# sch_LIMA_Driver.net
KiCad netlist of a schematic drawn in Altium Designer
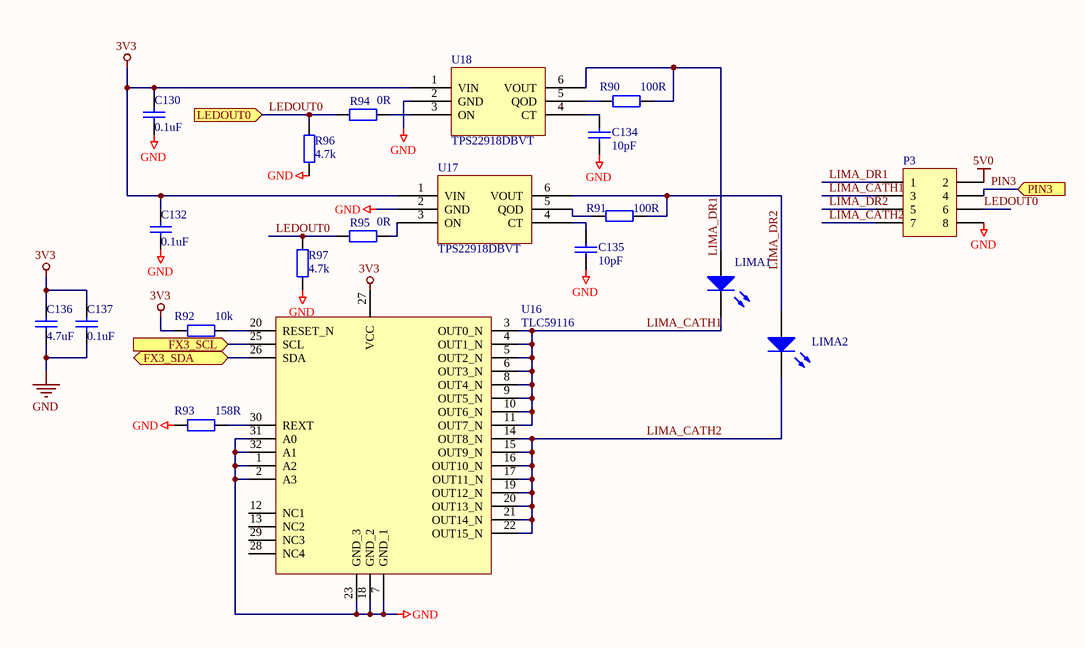
[diagram p0: sch_LIMA_Driver.SchDoc]

(export (version "E")
  (design (tool "Eeschema 10.0.6"))
  (components
    (comp (ref "C130")
      (value "0.1uF")
      (footprint "0402C_L")
      (description "Capacitor")
      (fields (field (name "Comment") "1uF") (field (name "PUBLISHER") "Altium Limited"))
      (libsource (lib "Miscellaneous Devices") (part "Cap"))
    )
    (comp (ref "C132")
      (value "0.1uF")
      (footprint "0402C_L")
      (description "Capacitor")
      (fields (field (name "Comment") "1uF") (field (name "PUBLISHER") "Altium Limited"))
      (libsource (lib "Miscellaneous Devices") (part "Cap"))
    )
    (comp (ref "C134")
      (value "10pF")
      (footprint "0402C_L")
      (description "Capacitor")
      (fields (field (name "PUBLISHER") "Altium Limited"))
      (libsource (lib "Miscellaneous Devices") (part "Cap"))
    )
    (comp (ref "C135")
      (value "10pF")
      (footprint "0402C_L")
      (description "Capacitor")
      (fields (field (name "PUBLISHER") "Altium Limited"))
      (libsource (lib "Miscellaneous Devices") (part "Cap"))
    )
    (comp (ref "C136")
      (value "4.7uF")
      (description "Capacitor")
      (fields (field (name "PUBLISHER") "Altium Limited"))
      (libsource (lib "Miscellaneous Devices") (part "Cap"))
    )
    (comp (ref "C137")
      (value "0.1uF")
      (footprint "0402C")
      (description "Capacitor")
      (fields (field (name "PUBLISHER") "Altium Limited"))
      (libsource (lib "Miscellaneous Devices") (part "Cap"))
    )
    (comp (ref "LIMA1") (value "LIMA") (description "发光二级管") (libsource (lib "TXW") (part "LED")))
    (comp (ref "LIMA2") (value "LIMA") (description "发光二级管") (libsource (lib "TXW") (part "LED")))
    (comp (ref "P3")
      (value "Header 4X2")
      (footprint "HDR2X4")
      (description "Header, 4-Pin, Dual row")
      (fields (field (name "PUBLISHER") "Altium Limited"))
      (libsource (lib "SZG") (part "Header 4X2"))
    )
    (comp (ref "R90")
      (value "100R")
      (footprint "0402R")
      (description "Resistor")
      (fields (field (name "PUBLISHER") "Altium Limited"))
      (libsource (lib "") (part "Resistor_1"))
    )
    (comp (ref "R91")
      (value "100R")
      (footprint "0402R")
      (description "Resistor")
      (fields (field (name "PUBLISHER") "Altium Limited"))
      (libsource (lib "") (part "Resistor_1"))
    )
    (comp (ref "R92")
      (value "10k")
      (footprint "0402R")
      (description "Resistor")
      (fields (field (name "PUBLISHER") "Altium Limited"))
      (libsource (lib "") (part "Resistor_1"))
    )
    (comp (ref "R93")
      (value "158R")
      (footprint "0402R")
      (description "Resistor")
      (fields (field (name "PUBLISHER") "Altium Limited"))
      (libsource (lib "") (part "Resistor_1"))
    )
    (comp (ref "R94")
      (value "0R")
      (footprint "0402R")
      (description "Resistor")
      (fields (field (name "PUBLISHER") "Altium Limited"))
      (libsource (lib "") (part "Resistor_1"))
    )
    (comp (ref "R95")
      (value "0R")
      (footprint "0402R")
      (description "Resistor")
      (fields (field (name "PUBLISHER") "Altium Limited"))
      (libsource (lib "") (part "Resistor_1"))
    )
    (comp (ref "R96")
      (value "4.7k")
      (footprint "0402R")
      (description "Resistor")
      (fields (field (name "PUBLISHER") "Altium Limited"))
      (libsource (lib "SZG") (part "Resistor"))
    )
    (comp (ref "R97")
      (value "4.7k")
      (footprint "0402R")
      (description "Resistor")
      (fields (field (name "PUBLISHER") "Altium Limited"))
      (libsource (lib "SZG") (part "Resistor"))
    )
    (comp (ref "U16") (value "TLC59116") (libsource (lib "SZG") (part "TLC59116")))
    (comp (ref "U17") (value "TPS22918DBVT") (libsource (lib "SZG") (part "TPS22918DBVT")))
    (comp (ref "U18") (value "TPS22918DBVT") (libsource (lib "SZG") (part "TPS22918DBVT")))
  )
  (nets
    (net (code "1") (name "/FX3_SCL") (class "Default")
      (node (ref "U16") (pin "25") (pinfunction "SCL_25") (pintype "passive"))
    )
    (net (code "2") (name "/FX3_SDA") (class "Default")
      (node (ref "U16") (pin "26") (pinfunction "SDA_26") (pintype "passive"))
    )
    (net (code "3") (name "/LEDOUT0") (class "Default")
      (node (ref "P3") (pin "6") (pinfunction "6_6") (pintype "passive"))
      (node (ref "R94") (pin "2") (pinfunction "2_2") (pintype "passive"))
      (node (ref "R95") (pin "2") (pinfunction "2_2") (pintype "passive"))
      (node (ref "R96") (pin "2") (pinfunction "2_2") (pintype "passive"))
      (node (ref "R97") (pin "2") (pinfunction "2_2") (pintype "passive"))
    )
    (net (code "4") (name "/LIMA_CATH1") (class "Default")
      (node (ref "LIMA1") (pin "2") (pinfunction "K_2") (pintype "passive"))
      (node (ref "P3") (pin "3") (pinfunction "3_3") (pintype "passive"))
      (node (ref "U16") (pin "10") (pinfunction "OUT6_N_10") (pintype "passive"))
      (node (ref "U16") (pin "11") (pinfunction "OUT7_N_11") (pintype "passive"))
      (node (ref "U16") (pin "3") (pinfunction "OUT0_N_3") (pintype "passive"))
      (node (ref "U16") (pin "4") (pinfunction "OUT1_N_4") (pintype "passive"))
      (node (ref "U16") (pin "5") (pinfunction "OUT2_N_5") (pintype "passive"))
      (node (ref "U16") (pin "6") (pinfunction "OUT3_N_6") (pintype "passive"))
      (node (ref "U16") (pin "8") (pinfunction "OUT4_N_8") (pintype "passive"))
      (node (ref "U16") (pin "9") (pinfunction "OUT5_N_9") (pintype "passive"))
    )
    (net (code "5") (name "/LIMA_CATH2") (class "Default")
      (node (ref "LIMA2") (pin "2") (pinfunction "K_2") (pintype "passive"))
      (node (ref "P3") (pin "7") (pinfunction "7_7") (pintype "passive"))
      (node (ref "U16") (pin "14") (pinfunction "OUT8_N_14") (pintype "passive"))
      (node (ref "U16") (pin "15") (pinfunction "OUT9_N_15") (pintype "passive"))
      (node (ref "U16") (pin "16") (pinfunction "OUT10_N_16") (pintype "passive"))
      (node (ref "U16") (pin "17") (pinfunction "OUT11_N_17") (pintype "passive"))
      (node (ref "U16") (pin "19") (pinfunction "OUT12_N_19") (pintype "passive"))
      (node (ref "U16") (pin "20") (pinfunction "OUT13_N_20") (pintype "passive"))
      (node (ref "U16") (pin "21") (pinfunction "OUT14_N_21") (pintype "passive"))
      (node (ref "U16") (pin "22") (pinfunction "OUT15_N_22") (pintype "passive"))
    )
    (net (code "6") (name "/LIMA_DR1") (class "Default")
      (node (ref "P3") (pin "1") (pinfunction "1_1") (pintype "passive"))
    )
    (net (code "7") (name "/LIMA_DR2") (class "Default")
      (node (ref "LIMA2") (pin "1") (pinfunction "A_1") (pintype "passive"))
      (node (ref "P3") (pin "5") (pinfunction "5_5") (pintype "passive"))
      (node (ref "R91") (pin "1") (pinfunction "1_1") (pintype "passive"))
      (node (ref "U17") (pin "6") (pinfunction "VOUT_6") (pintype "passive"))
    )
    (net (code "8") (name "/PIN3") (class "Default")
      (node (ref "P3") (pin "4") (pinfunction "4_4") (pintype "passive"))
    )
    (net (code "9") (name "3V3") (class "Default")
      (node (ref "C130") (pin "2") (pinfunction "2_2") (pintype "passive"))
      (node (ref "C132") (pin "2") (pinfunction "2_2") (pintype "passive"))
      (node (ref "C136") (pin "2") (pinfunction "2_2") (pintype "passive"))
      (node (ref "C137") (pin "2") (pinfunction "2_2") (pintype "passive"))
      (node (ref "R92") (pin "2") (pinfunction "2_2") (pintype "passive"))
      (node (ref "U16") (pin "27") (pinfunction "VCC_27") (pintype "passive"))
      (node (ref "U17") (pin "1") (pinfunction "VIN_1") (pintype "passive"))
      (node (ref "U18") (pin "1") (pinfunction "VIN_1") (pintype "passive"))
    )
    (net (code "10") (name "5V0") (class "Default")
      (node (ref "P3") (pin "2") (pinfunction "2_2") (pintype "passive"))
    )
    (net (code "11") (name "GND") (class "Default")
      (node (ref "C130") (pin "1") (pinfunction "1_1") (pintype "passive"))
      (node (ref "C132") (pin "1") (pinfunction "1_1") (pintype "passive"))
      (node (ref "C134") (pin "1") (pinfunction "1_1") (pintype "passive"))
      (node (ref "C135") (pin "1") (pinfunction "1_1") (pintype "passive"))
      (node (ref "C136") (pin "1") (pinfunction "1_1") (pintype "passive"))
      (node (ref "C137") (pin "1") (pinfunction "1_1") (pintype "passive"))
      (node (ref "P3") (pin "8") (pinfunction "8_8") (pintype "passive"))
      (node (ref "R93") (pin "2") (pinfunction "2_2") (pintype "passive"))
      (node (ref "R96") (pin "1") (pinfunction "1_1") (pintype "passive"))
      (node (ref "R97") (pin "1") (pinfunction "1_1") (pintype "passive"))
      (node (ref "U16") (pin "1") (pinfunction "A2_1") (pintype "passive"))
      (node (ref "U16") (pin "18") (pinfunction "GND_2_18") (pintype "passive"))
      (node (ref "U16") (pin "2") (pinfunction "A3_2") (pintype "passive"))
      (node (ref "U16") (pin "23") (pinfunction "GND_3_23") (pintype "passive"))
      (node (ref "U16") (pin "31") (pinfunction "A0_31") (pintype "passive"))
      (node (ref "U16") (pin "32") (pinfunction "A1_32") (pintype "passive"))
      (node (ref "U16") (pin "7") (pinfunction "GND_1_7") (pintype "passive"))
      (node (ref "U17") (pin "2") (pinfunction "GND_2") (pintype "passive"))
      (node (ref "U18") (pin "2") (pinfunction "GND_2") (pintype "passive"))
    )
    (net (code "12") (name "Net-(LIMA1-A)") (class "Default")
      (node (ref "LIMA1") (pin "1") (pinfunction "A_1") (pintype "passive"))
      (node (ref "R90") (pin "1") (pinfunction "1_1") (pintype "passive"))
      (node (ref "U18") (pin "6") (pinfunction "VOUT_6") (pintype "passive"))
    )
    (net (code "13") (name "Net-(U16-RESET_N)") (class "Default")
      (node (ref "R92") (pin "1") (pinfunction "1_1") (pintype "passive"))
      (node (ref "U16") (pin "20") (pinfunction "RESET_N_20") (pintype "passive"))
    )
    (net (code "14") (name "Net-(U16-REXT)") (class "Default")
      (node (ref "R93") (pin "1") (pinfunction "1_1") (pintype "passive"))
      (node (ref "U16") (pin "30") (pinfunction "REXT_30") (pintype "passive"))
    )
    (net (code "15") (name "Net-(U17-CT)") (class "Default")
      (node (ref "C135") (pin "2") (pinfunction "2_2") (pintype "passive"))
      (node (ref "U17") (pin "4") (pinfunction "CT_4") (pintype "passive"))
    )
    (net (code "16") (name "Net-(U17-ON)") (class "Default")
      (node (ref "R95") (pin "1") (pinfunction "1_1") (pintype "passive"))
      (node (ref "U17") (pin "3") (pinfunction "ON_3") (pintype "passive"))
    )
    (net (code "17") (name "Net-(U17-QOD)") (class "Default")
      (node (ref "R91") (pin "2") (pinfunction "2_2") (pintype "passive"))
      (node (ref "U17") (pin "5") (pinfunction "QOD_5") (pintype "passive"))
    )
    (net (code "18") (name "Net-(U18-CT)") (class "Default")
      (node (ref "C134") (pin "2") (pinfunction "2_2") (pintype "passive"))
      (node (ref "U18") (pin "4") (pinfunction "CT_4") (pintype "passive"))
    )
    (net (code "19") (name "Net-(U18-ON)") (class "Default")
      (node (ref "R94") (pin "1") (pinfunction "1_1") (pintype "passive"))
      (node (ref "U18") (pin "3") (pinfunction "ON_3") (pintype "passive"))
    )
    (net (code "20") (name "Net-(U18-QOD)") (class "Default")
      (node (ref "R90") (pin "2") (pinfunction "2_2") (pintype "passive"))
      (node (ref "U18") (pin "5") (pinfunction "QOD_5") (pintype "passive"))
    )
    (net (code "21") (name "unconnected-(U16-NC1-Pad12)") (class "Default")
      (node (ref "U16") (pin "12") (pinfunction "NC1_12") (pintype "passive"))
    )
    (net (code "22") (name "unconnected-(U16-NC2-Pad13)") (class "Default")
      (node (ref "U16") (pin "13") (pinfunction "NC2_13") (pintype "passive"))
    )
    (net (code "23") (name "unconnected-(U16-NC3-Pad29)") (class "Default")
      (node (ref "U16") (pin "29") (pinfunction "NC3_29") (pintype "passive"))
    )
    (net (code "24") (name "unconnected-(U16-NC4-Pad28)") (class "Default")
      (node (ref "U16") (pin "28") (pinfunction "NC4_28") (pintype "passive"))
    )
  )
)
